# KMO_IO_MV1_3.net
KiCad netlist of a schematic drawn in EAGLE
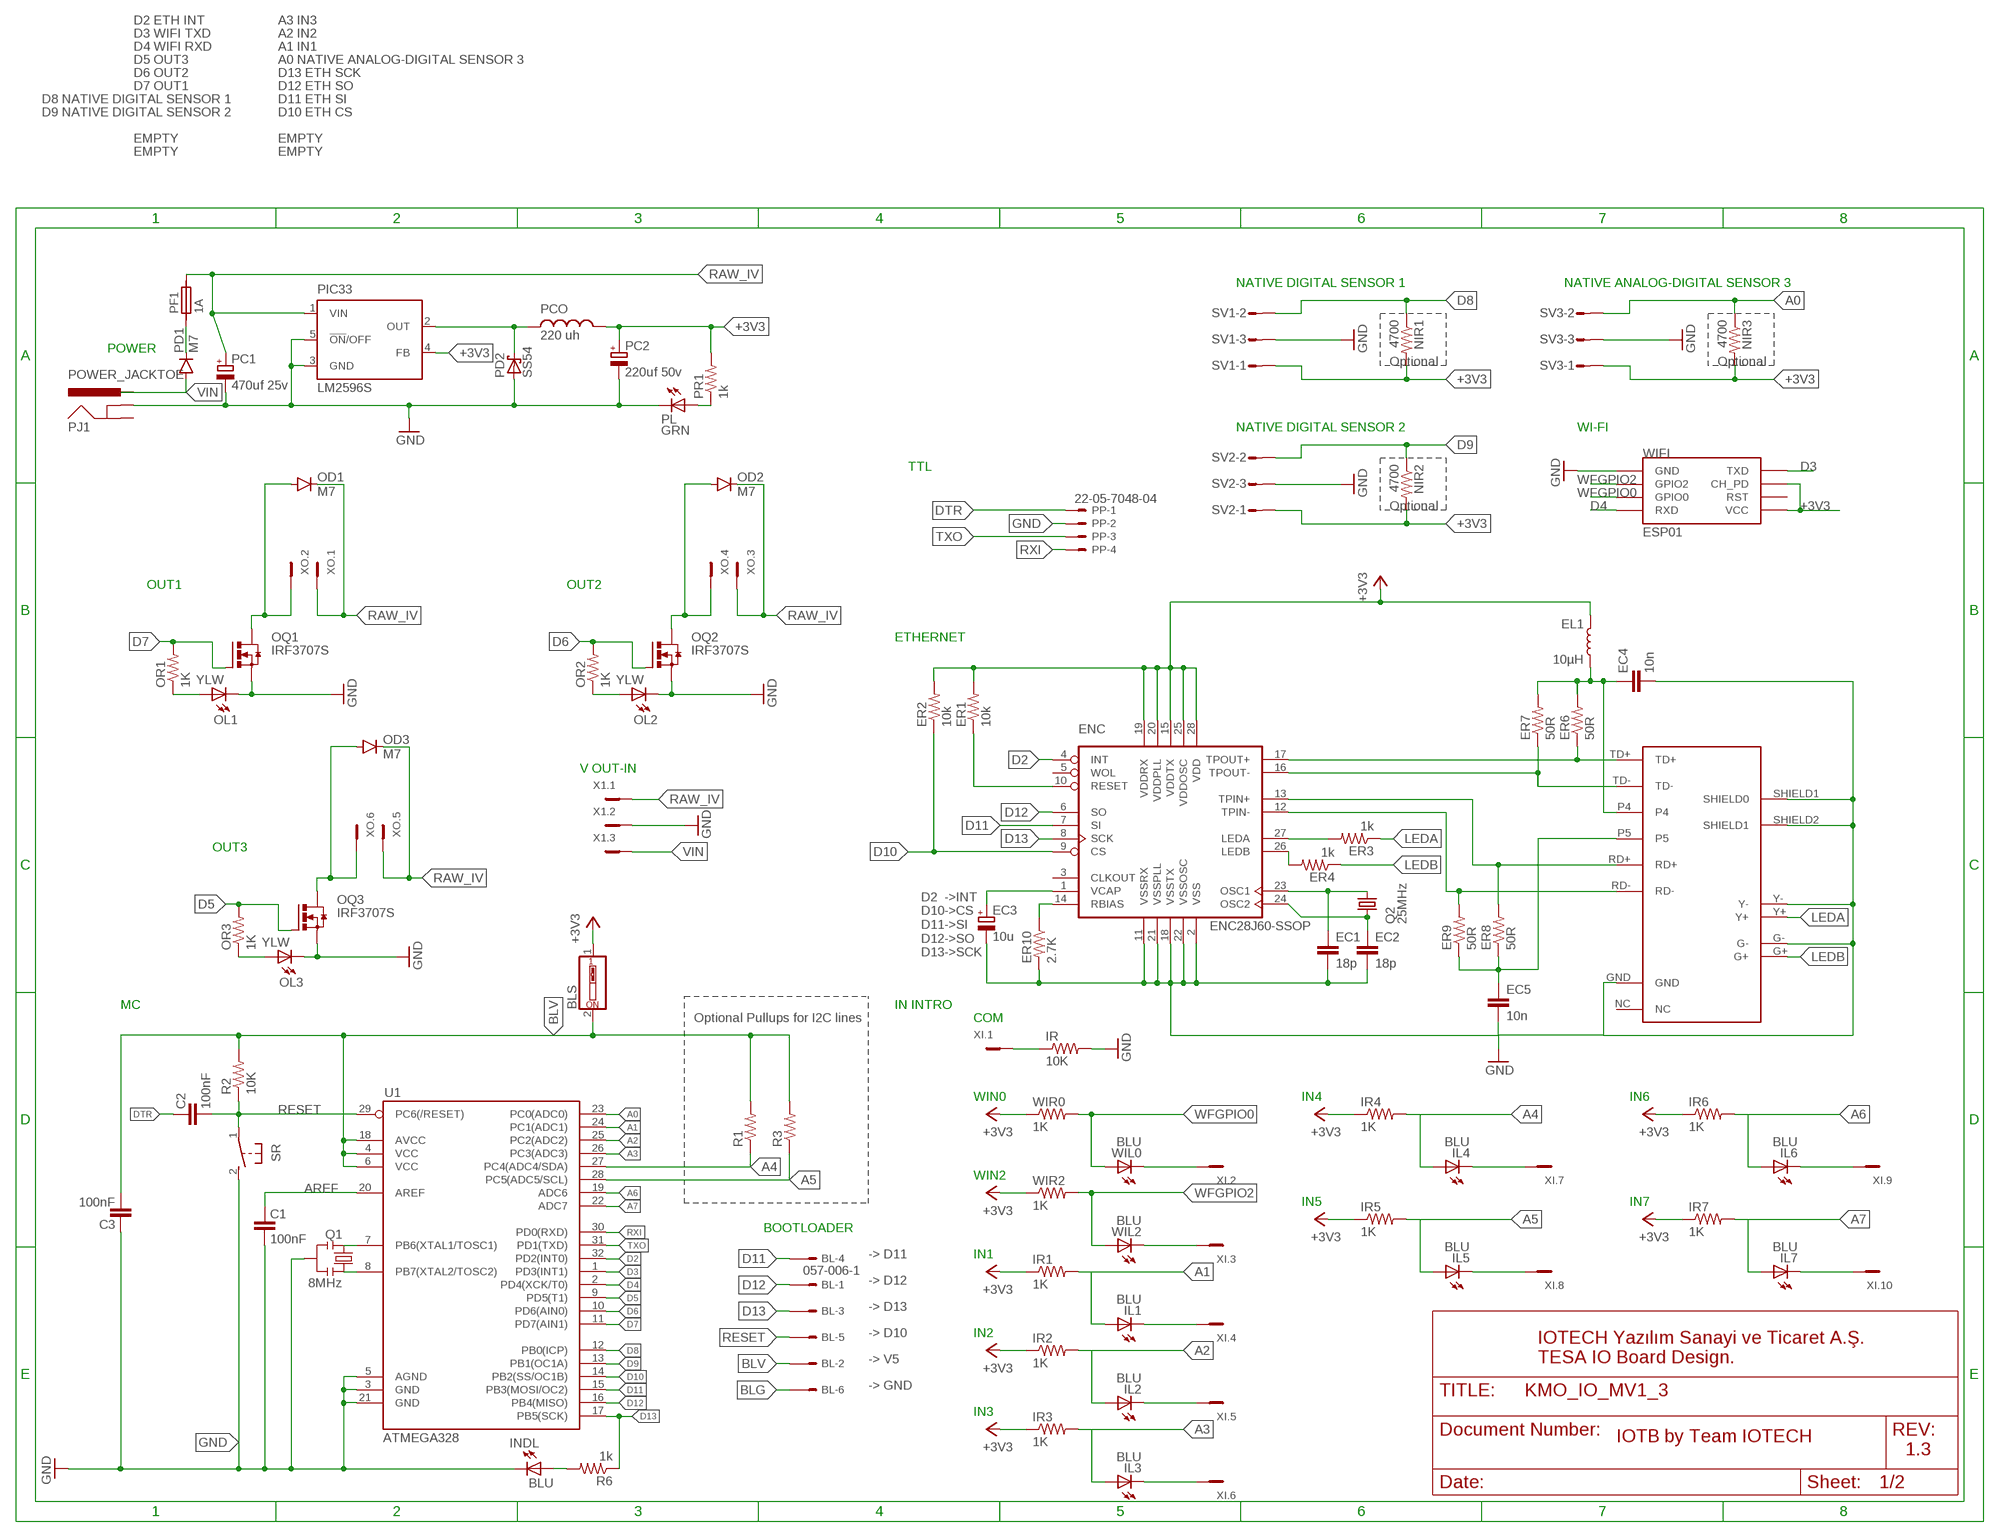
[diagram p0: schematic, sheet 1]
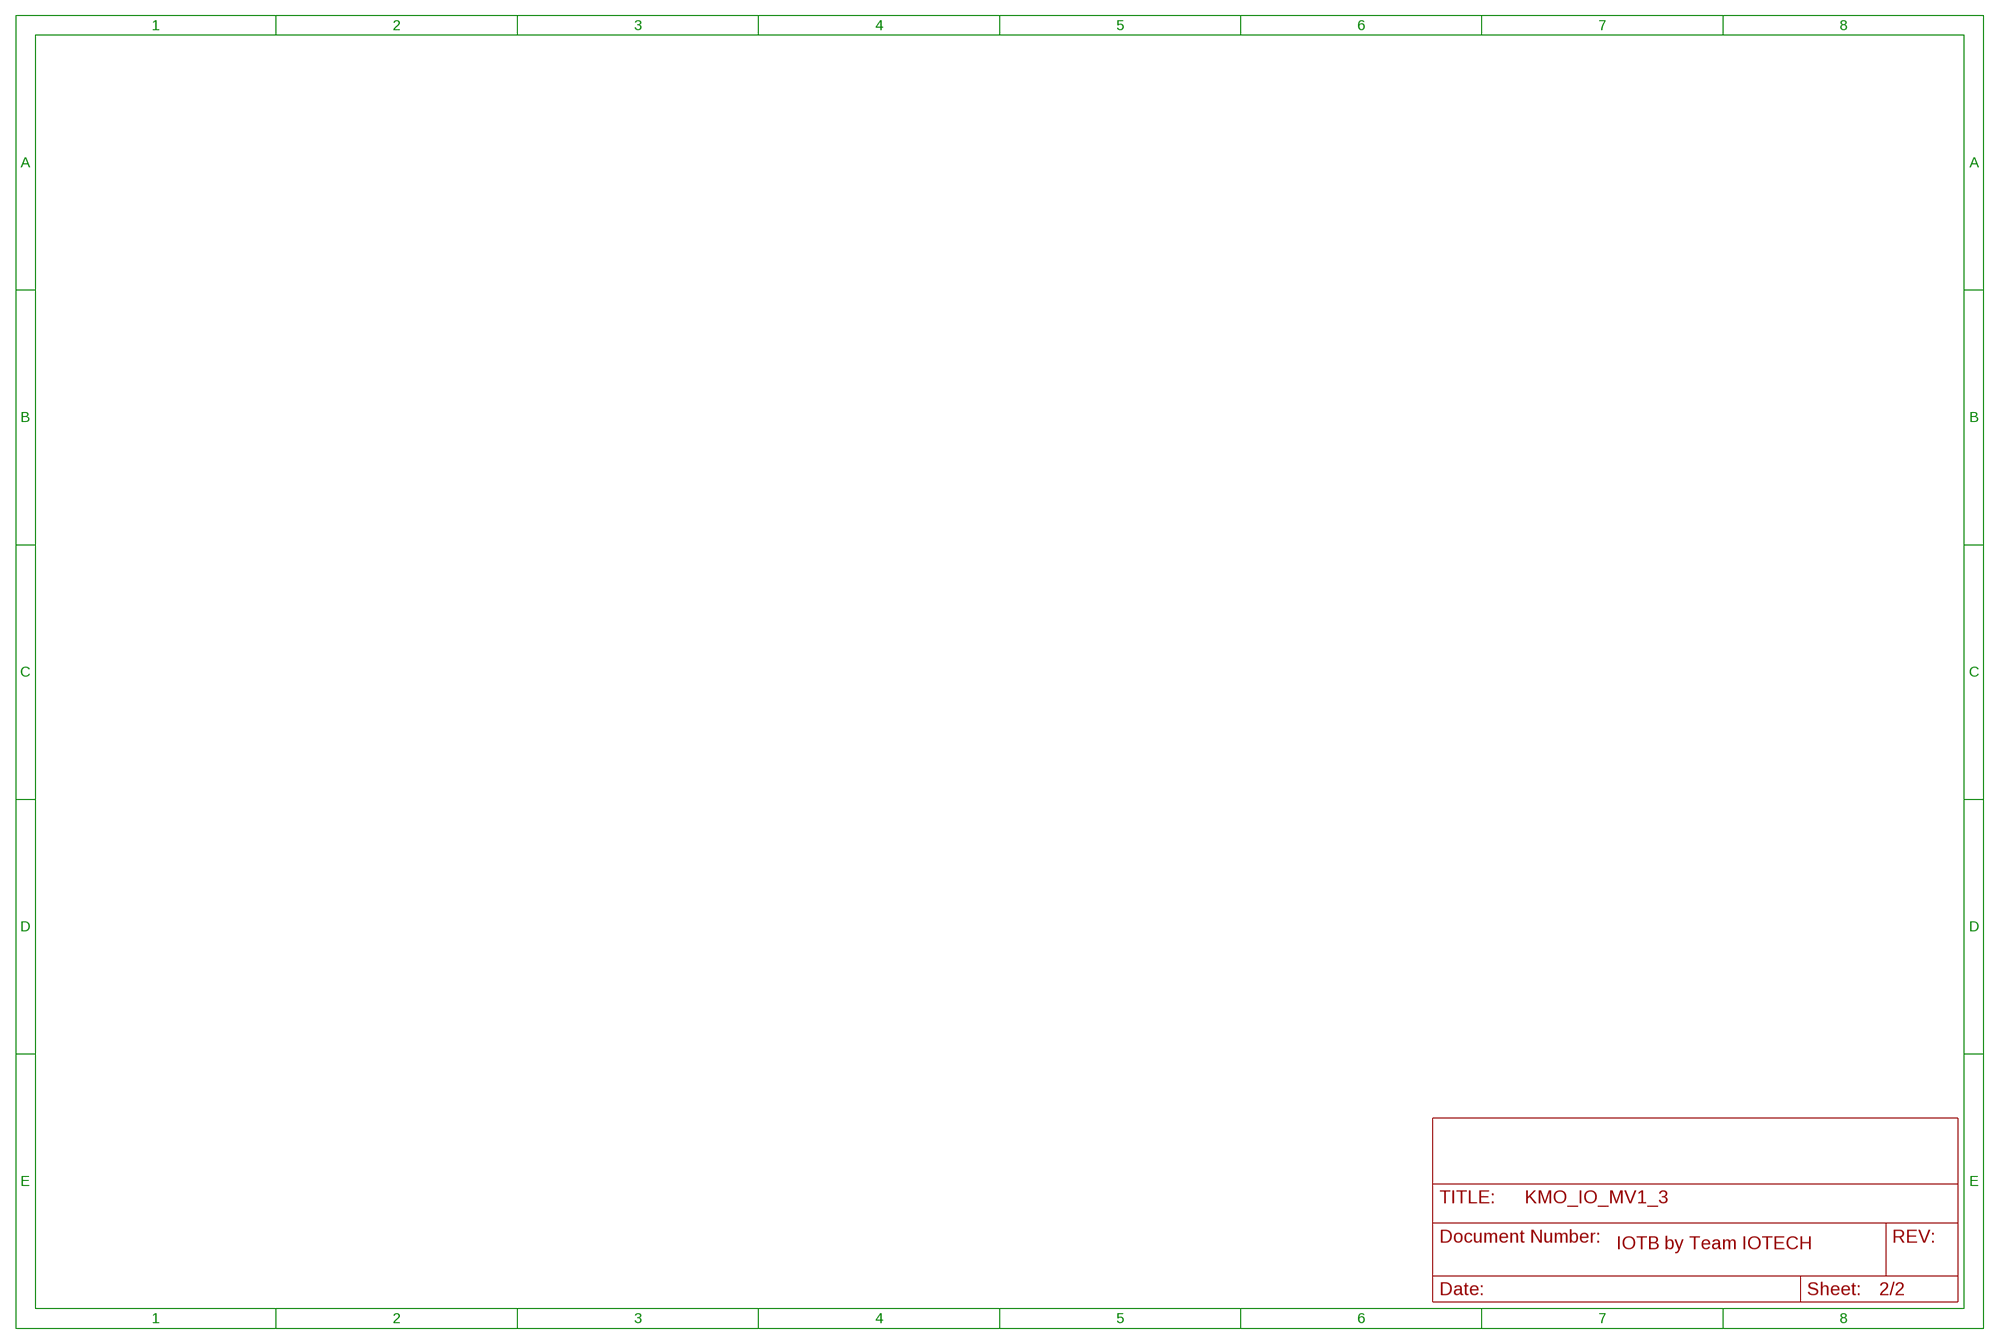
[diagram p1: schematic, sheet 2]

(export (version "E")
  (design (tool "Eeschema 10.0.6"))
  (components
    (comp (ref "BL")
      (value "057-006-1")
      (footprint "eagle-import:057-006-1")
      (libsource (lib "eagle-import") (part "057-006-1"))
    )
    (comp (ref "BLS")
      (value "SW_DIP-1")
      (footprint "eagle-import:EDG-01")
      (libsource (lib "eagle-import") (part "SW_DIP-1"))
    )
    (comp (ref "C1")
      (value "100nF")
      (footprint "eagle-import:0805")
      (libsource (lib "eagle-import") (part "CAP0805"))
    )
    (comp (ref "C2")
      (value "100nF")
      (footprint "eagle-import:0805")
      (libsource (lib "eagle-import") (part "CAP0805"))
    )
    (comp (ref "C3")
      (value "100nF")
      (footprint "eagle-import:0805")
      (libsource (lib "eagle-import") (part "CAP0805"))
    )
    (comp (ref "EC1")
      (value "18p")
      (footprint "eagle-import:0805")
      (libsource (lib "eagle-import") (part "CAP0805"))
    )
    (comp (ref "EC2")
      (value "18p")
      (footprint "eagle-import:0805")
      (libsource (lib "eagle-import") (part "CAP0805"))
    )
    (comp (ref "EC3")
      (value "10u")
      (footprint "eagle-import:CT3216")
      (libsource (lib "eagle-import") (part "CPOL-EUCT3216"))
    )
    (comp (ref "EC4")
      (value "10n")
      (footprint "eagle-import:0805")
      (libsource (lib "eagle-import") (part "CAP0805"))
    )
    (comp (ref "EC5")
      (value "10n")
      (footprint "eagle-import:0805")
      (libsource (lib "eagle-import") (part "CAP0805"))
    )
    (comp (ref "EL1")
      (value "10µH")
      (footprint "eagle-import:0805")
      (libsource (lib "eagle-import") (part "INDUCTOR-0805-3.3UH"))
    )
    (comp (ref "ENC")
      (value "ENC28J60-SSOP")
      (footprint "eagle-import:SSOP28")
      (libsource (lib "eagle-import") (part "ENC28J60-SSOP"))
    )
    (comp (ref "ER1")
      (value "10k")
      (footprint "eagle-import:0805")
      (libsource (lib "eagle-import") (part "RESISTOR0805-RES"))
    )
    (comp (ref "ER2")
      (value "10k")
      (footprint "eagle-import:0805")
      (libsource (lib "eagle-import") (part "RESISTOR0805-RES"))
    )
    (comp (ref "ER3")
      (value "1k")
      (footprint "eagle-import:0805")
      (libsource (lib "eagle-import") (part "RESISTOR0805-RES"))
    )
    (comp (ref "ER4")
      (value "1k")
      (footprint "eagle-import:0805")
      (libsource (lib "eagle-import") (part "RESISTOR0805-RES"))
    )
    (comp (ref "ER6")
      (value "50R")
      (footprint "eagle-import:0805")
      (libsource (lib "eagle-import") (part "RESISTOR0805-RES"))
    )
    (comp (ref "ER7")
      (value "50R")
      (footprint "eagle-import:0805")
      (libsource (lib "eagle-import") (part "RESISTOR0805-RES"))
    )
    (comp (ref "ER8")
      (value "50R")
      (footprint "eagle-import:0805")
      (libsource (lib "eagle-import") (part "RESISTOR0805-RES"))
    )
    (comp (ref "ER9")
      (value "50R")
      (footprint "eagle-import:0805")
      (libsource (lib "eagle-import") (part "RESISTOR0805-RES"))
    )
    (comp (ref "ER10")
      (value "2.7K")
      (footprint "eagle-import:0805")
      (libsource (lib "eagle-import") (part "RESISTOR0805-RES"))
    )
    (comp (ref "IL1")
      (value "BLU")
      (footprint "eagle-import:CHIP-LED0805")
      (libsource (lib "eagle-import") (part "LEDCHIP-LED0805"))
    )
    (comp (ref "IL2")
      (value "BLU")
      (footprint "eagle-import:CHIP-LED0805")
      (libsource (lib "eagle-import") (part "LEDCHIP-LED0805"))
    )
    (comp (ref "IL3")
      (value "BLU")
      (footprint "eagle-import:CHIP-LED0805")
      (libsource (lib "eagle-import") (part "LEDCHIP-LED0805"))
    )
    (comp (ref "IL4")
      (value "BLU")
      (footprint "eagle-import:CHIP-LED0805")
      (libsource (lib "eagle-import") (part "LEDCHIP-LED0805"))
    )
    (comp (ref "IL5")
      (value "BLU")
      (footprint "eagle-import:CHIP-LED0805")
      (libsource (lib "eagle-import") (part "LEDCHIP-LED0805"))
    )
    (comp (ref "IL6")
      (value "BLU")
      (footprint "eagle-import:CHIP-LED0805")
      (libsource (lib "eagle-import") (part "LEDCHIP-LED0805"))
    )
    (comp (ref "IL7")
      (value "BLU")
      (footprint "eagle-import:CHIP-LED0805")
      (libsource (lib "eagle-import") (part "LEDCHIP-LED0805"))
    )
    (comp (ref "INDL")
      (value "BLU")
      (footprint "eagle-import:CHIP-LED0805")
      (libsource (lib "eagle-import") (part "LEDCHIP-LED0805"))
    )
    (comp (ref "IR")
      (value "10K")
      (footprint "eagle-import:0805")
      (libsource (lib "eagle-import") (part "RESISTOR0805-RES"))
    )
    (comp (ref "IR1")
      (value "1K")
      (footprint "eagle-import:0805")
      (libsource (lib "eagle-import") (part "RESISTOR0805-RES"))
    )
    (comp (ref "IR2")
      (value "1K")
      (footprint "eagle-import:0805")
      (libsource (lib "eagle-import") (part "RESISTOR0805-RES"))
    )
    (comp (ref "IR3")
      (value "1K")
      (footprint "eagle-import:0805")
      (libsource (lib "eagle-import") (part "RESISTOR0805-RES"))
    )
    (comp (ref "IR4")
      (value "1K")
      (footprint "eagle-import:0805")
      (libsource (lib "eagle-import") (part "RESISTOR0805-RES"))
    )
    (comp (ref "IR5")
      (value "1K")
      (footprint "eagle-import:0805")
      (libsource (lib "eagle-import") (part "RESISTOR0805-RES"))
    )
    (comp (ref "IR6")
      (value "1K")
      (footprint "eagle-import:0805")
      (libsource (lib "eagle-import") (part "RESISTOR0805-RES"))
    )
    (comp (ref "IR7")
      (value "1K")
      (footprint "eagle-import:0805")
      (libsource (lib "eagle-import") (part "RESISTOR0805-RES"))
    )
    (comp (ref "NIR1")
      (value "4700")
      (footprint "eagle-import:0805")
      (libsource (lib "eagle-import") (part "RESISTOR0805-RES"))
    )
    (comp (ref "NIR2")
      (value "4700")
      (footprint "eagle-import:0805")
      (libsource (lib "eagle-import") (part "RESISTOR0805-RES"))
    )
    (comp (ref "NIR3")
      (value "4700")
      (footprint "eagle-import:0805")
      (libsource (lib "eagle-import") (part "RESISTOR0805-RES"))
    )
    (comp (ref "OD1")
      (value "M7")
      (footprint "eagle-import:SMA-DIODE")
      (libsource (lib "eagle-import") (part "DIODESMA"))
    )
    (comp (ref "OD2")
      (value "M7")
      (footprint "eagle-import:SMA-DIODE")
      (libsource (lib "eagle-import") (part "DIODESMA"))
    )
    (comp (ref "OD3")
      (value "M7")
      (footprint "eagle-import:SMA-DIODE")
      (libsource (lib "eagle-import") (part "DIODESMA"))
    )
    (comp (ref "OL1")
      (value "YLW")
      (footprint "eagle-import:CHIP-LED0805")
      (libsource (lib "eagle-import") (part "LEDCHIP-LED0805"))
    )
    (comp (ref "OL2")
      (value "YLW")
      (footprint "eagle-import:CHIP-LED0805")
      (libsource (lib "eagle-import") (part "LEDCHIP-LED0805"))
    )
    (comp (ref "OL3")
      (value "YLW")
      (footprint "eagle-import:CHIP-LED0805")
      (libsource (lib "eagle-import") (part "LEDCHIP-LED0805"))
    )
    (comp (ref "OQ1")
      (value "IRF3707S")
      (footprint "eagle-import:D2PACK")
      (libsource (lib "eagle-import") (part "IRF3704S"))
    )
    (comp (ref "OQ2")
      (value "IRF3707S")
      (footprint "eagle-import:D2PACK")
      (libsource (lib "eagle-import") (part "IRF3704S"))
    )
    (comp (ref "OQ3")
      (value "IRF3707S")
      (footprint "eagle-import:D2PACK")
      (libsource (lib "eagle-import") (part "IRF3704S"))
    )
    (comp (ref "OR1")
      (value "1K")
      (footprint "eagle-import:0805")
      (libsource (lib "eagle-import") (part "RESISTOR0805-RES"))
    )
    (comp (ref "OR2")
      (value "1K")
      (footprint "eagle-import:0805")
      (libsource (lib "eagle-import") (part "RESISTOR0805-RES"))
    )
    (comp (ref "OR3")
      (value "1K")
      (footprint "eagle-import:0805")
      (libsource (lib "eagle-import") (part "RESISTOR0805-RES"))
    )
    (comp (ref "PC1")
      (value "470uf 25v")
      (footprint "eagle-import:140CLH-1010")
      (libsource (lib "eagle-import") (part "CPOL-EU140CLH-1010"))
    )
    (comp (ref "PC2")
      (value "220uf 50v")
      (footprint "eagle-import:140CLH-1010")
      (libsource (lib "eagle-import") (part "CPOL-EU140CLH-1010"))
    )
    (comp (ref "PCO")
      (value "220 uh")
      (footprint "eagle-import:MSS1260")
      (libsource (lib "eagle-import") (part "MSS1260"))
    )
    (comp (ref "PD1")
      (value "M7")
      (footprint "eagle-import:SMA-DIODE")
      (libsource (lib "eagle-import") (part "DIODESMA"))
    )
    (comp (ref "PD2")
      (value "SS54")
      (footprint "eagle-import:SMB")
      (libsource (lib "eagle-import") (part "SCHOTTKY-DIODESMD"))
    )
    (comp (ref "PF1")
      (value "1A")
      (footprint "eagle-import:1820")
      (libsource (lib "eagle-import") (part "SIBA194600"))
    )
    (comp (ref "PIC33")
      (value "LM2596S")
      (footprint "eagle-import:TO263-5")
      (fields (field (name "MF") "NATIONAL SEMICONDUCTOR") (field (name "MPN") "LM2596S-ADJ/NOPB"))
      (libsource (lib "eagle-import") (part "LM2596S"))
    )
    (comp (ref "PJ1")
      (value "POWER_JACKTOE")
      (footprint "eagle-import:POWER_JACK_SMD_OVERPASTE_TOE")
      (libsource (lib "eagle-import") (part "POWER_JACKTOE"))
    )
    (comp (ref "PL")
      (value "GRN")
      (footprint "eagle-import:CHIP-LED0805")
      (libsource (lib "eagle-import") (part "LEDCHIP-LED0805"))
    )
    (comp (ref "PP")
      (value "22-05-7048-04")
      (footprint "eagle-import:7395-04")
      (fields (field (name "MF") "MOLEX"))
      (libsource (lib "eagle-import") (part "22-?-0405-7048"))
    )
    (comp (ref "PR1")
      (value "1k")
      (footprint "eagle-import:0805")
      (libsource (lib "eagle-import") (part "RESISTOR0805-RES"))
    )
    (comp (ref "Q1")
      (value "8MHz")
      (footprint "eagle-import:RESONATOR-SMD-1_1")
      (libsource (lib "eagle-import") (part "RESONATOR1{colon}1"))
    )
    (comp (ref "Q2")
      (value "25MHz")
      (footprint "eagle-import:5.0X3.2_2")
      (libsource (lib "eagle-import") (part "KX-9B"))
    )
    (comp (ref "R1")
      (value "RESISTOR0805-RES")
      (footprint "eagle-import:0805")
      (libsource (lib "eagle-import") (part "RESISTOR0805-RES"))
    )
    (comp (ref "R2")
      (value "10K")
      (footprint "eagle-import:0805")
      (libsource (lib "eagle-import") (part "RESISTOR0805-RES"))
    )
    (comp (ref "R3")
      (value "RESISTOR0805-RES")
      (footprint "eagle-import:0805")
      (libsource (lib "eagle-import") (part "RESISTOR0805-RES"))
    )
    (comp (ref "R6")
      (value "1k")
      (footprint "eagle-import:0805")
      (libsource (lib "eagle-import") (part "RESISTOR0805-RES"))
    )
    (comp (ref "SR")
      (value "31-XX")
      (footprint "eagle-import:B3F-31XX")
      (fields (field (name "MPN") "B3F-3100"))
      (libsource (lib "eagle-import") (part "31-XX"))
    )
    (comp (ref "SV1")
      (value "S03P")
      (footprint "eagle-import:S03P")
      (libsource (lib "eagle-import") (part "S03P"))
    )
    (comp (ref "SV2")
      (value "S03P")
      (footprint "eagle-import:S03P")
      (libsource (lib "eagle-import") (part "S03P"))
    )
    (comp (ref "SV3")
      (value "S03P")
      (footprint "eagle-import:S03P")
      (libsource (lib "eagle-import") (part "S03P"))
    )
    (comp (ref "U$2")
      (value "HR911105A")
      (footprint "eagle-import:RJ45")
      (libsource (lib "eagle-import") (part "HR911105A"))
    )
    (comp (ref "U1")
      (value "ATMEGA328")
      (footprint "eagle-import:TQFP32-08")
      (libsource (lib "eagle-import") (part "ATMEGA168"))
    )
    (comp (ref "WIFI")
      (value "ESP01")
      (footprint "eagle-import:ESP01")
      (libsource (lib "eagle-import") (part "ESP01"))
    )
    (comp (ref "WIL0")
      (value "BLU")
      (footprint "eagle-import:CHIP-LED0805")
      (libsource (lib "eagle-import") (part "LEDCHIP-LED0805"))
    )
    (comp (ref "WIL2")
      (value "BLU")
      (footprint "eagle-import:CHIP-LED0805")
      (libsource (lib "eagle-import") (part "LEDCHIP-LED0805"))
    )
    (comp (ref "WIR0")
      (value "1K")
      (footprint "eagle-import:0805")
      (libsource (lib "eagle-import") (part "RESISTOR0805-RES"))
    )
    (comp (ref "WIR2")
      (value "1K")
      (footprint "eagle-import:0805")
      (libsource (lib "eagle-import") (part "RESISTOR0805-RES"))
    )
    (comp (ref "X1")
      (value "MC3")
      (footprint "eagle-import:MC3")
      (libsource (lib "eagle-import") (part "MC3"))
    )
    (comp (ref "XI")
      (value "MC10")
      (footprint "eagle-import:MC10")
      (libsource (lib "eagle-import") (part "MC10"))
    )
    (comp (ref "XO")
      (value "MC6")
      (footprint "eagle-import:MC6")
      (libsource (lib "eagle-import") (part "MC6"))
    )
  )
  (nets
    (net (code "1") (name "+3V3") (class "Default")
      (node (ref "BLS") (pin "1") (pinfunction "1_1") (pintype "passive"))
      (node (ref "EL1") (pin "1") (pinfunction "1_1") (pintype "passive"))
      (node (ref "ENC") (pin "15") (pinfunction "VDDTX_15") (pintype "power_in"))
      (node (ref "ENC") (pin "19") (pinfunction "VDDRX_19") (pintype "power_in"))
      (node (ref "ENC") (pin "20") (pinfunction "VDDPLL_20") (pintype "power_in"))
      (node (ref "ENC") (pin "25") (pinfunction "VDDOSC_25") (pintype "power_in"))
      (node (ref "ENC") (pin "28") (pinfunction "VDD_28") (pintype "power_in"))
      (node (ref "ER1") (pin "2") (pinfunction "2_2") (pintype "passive"))
      (node (ref "ER2") (pin "2") (pinfunction "2_2") (pintype "passive"))
      (node (ref "IR1") (pin "1") (pinfunction "1_1") (pintype "passive"))
      (node (ref "IR2") (pin "1") (pinfunction "1_1") (pintype "passive"))
      (node (ref "IR3") (pin "1") (pinfunction "1_1") (pintype "passive"))
      (node (ref "IR4") (pin "1") (pinfunction "1_1") (pintype "passive"))
      (node (ref "IR5") (pin "1") (pinfunction "1_1") (pintype "passive"))
      (node (ref "IR6") (pin "1") (pinfunction "1_1") (pintype "passive"))
      (node (ref "IR7") (pin "1") (pinfunction "1_1") (pintype "passive"))
      (node (ref "NIR1") (pin "2") (pinfunction "2_2") (pintype "passive"))
      (node (ref "NIR2") (pin "2") (pinfunction "2_2") (pintype "passive"))
      (node (ref "NIR3") (pin "2") (pinfunction "2_2") (pintype "passive"))
      (node (ref "PC2") (pin "+") (pinfunction "+_+") (pintype "passive"))
      (node (ref "PCO") (pin "P$1") (pinfunction "P$1_P$1") (pintype "passive"))
      (node (ref "PIC33") (pin "4") (pinfunction "FB_4") (pintype "input"))
      (node (ref "PR1") (pin "2") (pinfunction "2_2") (pintype "passive"))
      (node (ref "SV1") (pin "1") (pinfunction "S_1") (pintype "passive"))
      (node (ref "SV2") (pin "1") (pinfunction "S_1") (pintype "passive"))
      (node (ref "SV3") (pin "1") (pinfunction "S_1") (pintype "passive"))
      (node (ref "WIFI") (pin "CH_PD") (pinfunction "CH_PD_CH_PD") (pintype "bidirectional"))
      (node (ref "WIFI") (pin "VCC") (pinfunction "VCC_VCC") (pintype "bidirectional"))
      (node (ref "WIR0") (pin "1") (pinfunction "1_1") (pintype "passive"))
      (node (ref "WIR2") (pin "1") (pinfunction "1_1") (pintype "passive"))
    )
    (net (code "2") (name "A0") (class "Default")
      (node (ref "NIR3") (pin "1") (pinfunction "1_1") (pintype "passive"))
      (node (ref "SV3") (pin "2") (pinfunction "S_2") (pintype "passive"))
      (node (ref "U1") (pin "23") (pinfunction "PC0(ADC0)_23") (pintype "bidirectional"))
    )
    (net (code "3") (name "A1") (class "Default")
      (node (ref "IL1") (pin "A") (pinfunction "A_A") (pintype "passive"))
      (node (ref "IR1") (pin "2") (pinfunction "2_2") (pintype "passive"))
      (node (ref "U1") (pin "24") (pinfunction "PC1(ADC1)_24") (pintype "bidirectional"))
    )
    (net (code "4") (name "A2") (class "Default")
      (node (ref "IL2") (pin "A") (pinfunction "A_A") (pintype "passive"))
      (node (ref "IR2") (pin "2") (pinfunction "2_2") (pintype "passive"))
      (node (ref "U1") (pin "25") (pinfunction "PC2(ADC2)_25") (pintype "bidirectional"))
    )
    (net (code "5") (name "A3") (class "Default")
      (node (ref "IL3") (pin "A") (pinfunction "A_A") (pintype "passive"))
      (node (ref "IR3") (pin "2") (pinfunction "2_2") (pintype "passive"))
      (node (ref "U1") (pin "26") (pinfunction "PC3(ADC3)_26") (pintype "bidirectional"))
    )
    (net (code "6") (name "A4") (class "Default")
      (node (ref "IL4") (pin "A") (pinfunction "A_A") (pintype "passive"))
      (node (ref "IR4") (pin "2") (pinfunction "2_2") (pintype "passive"))
      (node (ref "R1") (pin "1") (pinfunction "1_1") (pintype "passive"))
      (node (ref "U1") (pin "27") (pinfunction "PC4(ADC4/SDA)_27") (pintype "bidirectional"))
    )
    (net (code "7") (name "A5") (class "Default")
      (node (ref "IL5") (pin "A") (pinfunction "A_A") (pintype "passive"))
      (node (ref "IR5") (pin "2") (pinfunction "2_2") (pintype "passive"))
      (node (ref "R3") (pin "1") (pinfunction "1_1") (pintype "passive"))
      (node (ref "U1") (pin "28") (pinfunction "PC5(ADC5/SCL)_28") (pintype "bidirectional"))
    )
    (net (code "8") (name "A6") (class "Default")
      (node (ref "IL6") (pin "A") (pinfunction "A_A") (pintype "passive"))
      (node (ref "IR6") (pin "2") (pinfunction "2_2") (pintype "passive"))
      (node (ref "U1") (pin "19") (pinfunction "ADC6_19") (pintype "bidirectional"))
    )
    (net (code "9") (name "A7") (class "Default")
      (node (ref "IL7") (pin "A") (pinfunction "A_A") (pintype "passive"))
      (node (ref "IR7") (pin "2") (pinfunction "2_2") (pintype "passive"))
      (node (ref "U1") (pin "22") (pinfunction "ADC7_22") (pintype "bidirectional"))
    )
    (net (code "10") (name "AREF") (class "Default")
      (node (ref "C1") (pin "2") (pinfunction "2_2") (pintype "passive"))
      (node (ref "U1") (pin "20") (pinfunction "AREF_20") (pintype "bidirectional"))
    )
    (net (code "11") (name "BLG") (class "Default")
      (node (ref "BL") (pin "6") (pinfunction "S_6") (pintype "passive"))
    )
    (net (code "12") (name "BLV") (class "Default")
      (node (ref "BL") (pin "2") (pinfunction "S_2") (pintype "passive"))
      (node (ref "BLS") (pin "2") (pinfunction "2_2") (pintype "passive"))
      (node (ref "C3") (pin "1") (pinfunction "1_1") (pintype "passive"))
      (node (ref "R1") (pin "2") (pinfunction "2_2") (pintype "passive"))
      (node (ref "R2") (pin "2") (pinfunction "2_2") (pintype "passive"))
      (node (ref "R3") (pin "2") (pinfunction "2_2") (pintype "passive"))
      (node (ref "U1") (pin "18") (pinfunction "AVCC_18") (pintype "bidirectional"))
      (node (ref "U1") (pin "4") (pinfunction "VCC_4") (pintype "bidirectional"))
      (node (ref "U1") (pin "6") (pinfunction "VCC_6") (pintype "bidirectional"))
    )
    (net (code "13") (name "D2") (class "Default")
      (node (ref "ENC") (pin "4") (pinfunction "INT_4") (pintype "output"))
      (node (ref "U1") (pin "32") (pinfunction "PD2(INT0)_32") (pintype "bidirectional"))
    )
    (net (code "14") (name "D3") (class "Default")
      (node (ref "U1") (pin "1") (pinfunction "PD3(INT1)_1") (pintype "bidirectional"))
      (node (ref "WIFI") (pin "TX") (pinfunction "TXD_TX") (pintype "bidirectional"))
    )
    (net (code "15") (name "D4") (class "Default")
      (node (ref "U1") (pin "2") (pinfunction "PD4(XCK/T0)_2") (pintype "bidirectional"))
      (node (ref "WIFI") (pin "RX") (pinfunction "RXD_RX") (pintype "bidirectional"))
    )
    (net (code "16") (name "D5") (class "Default")
      (node (ref "OQ3") (pin "1") (pinfunction "G_1") (pintype "passive"))
      (node (ref "OR3") (pin "2") (pinfunction "2_2") (pintype "passive"))
      (node (ref "U1") (pin "9") (pinfunction "PD5(T1)_9") (pintype "bidirectional"))
    )
    (net (code "17") (name "D6") (class "Default")
      (node (ref "OQ2") (pin "1") (pinfunction "G_1") (pintype "passive"))
      (node (ref "OR2") (pin "2") (pinfunction "2_2") (pintype "passive"))
      (node (ref "U1") (pin "10") (pinfunction "PD6(AIN0)_10") (pintype "bidirectional"))
    )
    (net (code "18") (name "D7") (class "Default")
      (node (ref "OQ1") (pin "1") (pinfunction "G_1") (pintype "passive"))
      (node (ref "OR1") (pin "2") (pinfunction "2_2") (pintype "passive"))
      (node (ref "U1") (pin "11") (pinfunction "PD7(AIN1)_11") (pintype "bidirectional"))
    )
    (net (code "19") (name "D8") (class "Default")
      (node (ref "NIR1") (pin "1") (pinfunction "1_1") (pintype "passive"))
      (node (ref "SV1") (pin "2") (pinfunction "S_2") (pintype "passive"))
      (node (ref "U1") (pin "12") (pinfunction "PB0(ICP)_12") (pintype "bidirectional"))
    )
    (net (code "20") (name "D9") (class "Default")
      (node (ref "NIR2") (pin "1") (pinfunction "1_1") (pintype "passive"))
      (node (ref "SV2") (pin "2") (pinfunction "S_2") (pintype "passive"))
      (node (ref "U1") (pin "13") (pinfunction "PB1(OC1A)_13") (pintype "bidirectional"))
    )
    (net (code "21") (name "D10") (class "Default")
      (node (ref "ENC") (pin "9") (pinfunction "CS_9") (pintype "input"))
      (node (ref "ER2") (pin "1") (pinfunction "1_1") (pintype "passive"))
      (node (ref "U1") (pin "14") (pinfunction "PB2(SS/OC1B)_14") (pintype "bidirectional"))
    )
    (net (code "22") (name "D11") (class "Default")
      (node (ref "BL") (pin "4") (pinfunction "S_4") (pintype "passive"))
      (node (ref "ENC") (pin "7") (pinfunction "SI_7") (pintype "input"))
      (node (ref "U1") (pin "15") (pinfunction "PB3(MOSI/OC2)_15") (pintype "bidirectional"))
    )
    (net (code "23") (name "D12") (class "Default")
      (node (ref "BL") (pin "1") (pinfunction "S_1") (pintype "passive"))
      (node (ref "ENC") (pin "6") (pinfunction "SO_6") (pintype "output"))
      (node (ref "U1") (pin "16") (pinfunction "PB4(MISO)_16") (pintype "bidirectional"))
    )
    (net (code "24") (name "D13") (class "Default")
      (node (ref "BL") (pin "3") (pinfunction "S_3") (pintype "passive"))
      (node (ref "ENC") (pin "8") (pinfunction "SCK_8") (pintype "input"))
      (node (ref "R6") (pin "1") (pinfunction "1_1") (pintype "passive"))
      (node (ref "U1") (pin "17") (pinfunction "PB5(SCK)_17") (pintype "bidirectional"))
    )
    (net (code "25") (name "DTR") (class "Default")
      (node (ref "C2") (pin "2") (pinfunction "2_2") (pintype "passive"))
      (node (ref "PP") (pin "1") (pinfunction "S_1") (pintype "passive"))
    )
    (net (code "26") (name "GND") (class "Default")
      (node (ref "C1") (pin "1") (pinfunction "1_1") (pintype "passive"))
      (node (ref "C3") (pin "2") (pinfunction "2_2") (pintype "passive"))
      (node (ref "EC1") (pin "2") (pinfunction "2_2") (pintype "passive"))
      (node (ref "EC2") (pin "2") (pinfunction "2_2") (pintype "passive"))
      (node (ref "EC3") (pin "-") (pinfunction "-_-") (pintype "passive"))
      (node (ref "EC4") (pin "2") (pinfunction "2_2") (pintype "passive"))
      (node (ref "EC5") (pin "2") (pinfunction "2_2") (pintype "passive"))
      (node (ref "ENC") (pin "11") (pinfunction "VSSRX_11") (pintype "power_in"))
      (node (ref "ENC") (pin "18") (pinfunction "VSSTX_18") (pintype "power_in"))
      (node (ref "ENC") (pin "2") (pinfunction "VSS_2") (pintype "power_in"))
      (node (ref "ENC") (pin "21") (pinfunction "VSSPLL_21") (pintype "power_in"))
      (node (ref "ENC") (pin "22") (pinfunction "VSSOSC_22") (pintype "power_in"))
      (node (ref "ER10") (pin "2") (pinfunction "2_2") (pintype "passive"))
      (node (ref "INDL") (pin "C") (pinfunction "C_C") (pintype "passive"))
      (node (ref "IR") (pin "2") (pinfunction "2_2") (pintype "passive"))
      (node (ref "OL1") (pin "C") (pinfunction "C_C") (pintype "passive"))
      (node (ref "OL2") (pin "C") (pinfunction "C_C") (pintype "passive"))
      (node (ref "OL3") (pin "C") (pinfunction "C_C") (pintype "passive"))
      (node (ref "OQ1") (pin "3") (pinfunction "S_3") (pintype "passive"))
      (node (ref "OQ2") (pin "3") (pinfunction "S_3") (pintype "passive"))
      (node (ref "OQ3") (pin "3") (pinfunction "S_3") (pintype "passive"))
      (node (ref "PC1") (pin "-") (pinfunction "-_-") (pintype "passive"))
      (node (ref "PC2") (pin "-") (pinfunction "-_-") (pintype "passive"))
      (node (ref "PD2") (pin "A") (pinfunction "A_A") (pintype "passive"))
      (node (ref "PIC33") (pin "3") (pinfunction "GND_3") (pintype "power_in"))
      (node (ref "PIC33") (pin "5") (pinfunction "~{ON}/OFF_5") (pintype "input"))
      (node (ref "PJ1") (pin "GND") (pinfunction "GNDBREAK_GND") (pintype "bidirectional"))
      (node (ref "PL") (pin "C") (pinfunction "C_C") (pintype "passive"))
      (node (ref "PP") (pin "2") (pinfunction "S_2") (pintype "passive"))
      (node (ref "Q1") (pin "2") (pinfunction "2_2") (pintype "passive"))
      (node (ref "SR") (pin "2") (pinfunction "S_2") (pintype "passive"))
      (node (ref "SV1") (pin "3") (pinfunction "S_3") (pintype "passive"))
      (node (ref "SV2") (pin "3") (pinfunction "S_3") (pintype "passive"))
      (node (ref "SV3") (pin "3") (pinfunction "S_3") (pintype "passive"))
      (node (ref "U$2") (pin "G-") (pinfunction "G-_G-") (pintype "bidirectional"))
      (node (ref "U$2") (pin "GND") (pinfunction "GND_GND") (pintype "bidirectional"))
      (node (ref "U$2") (pin "SHIELD1") (pinfunction "SHIELD0_SHIELD1") (pintype "bidirectional"))
      (node (ref "U$2") (pin "SHIELD2") (pinfunction "SHIELD1_SHIELD2") (pintype "bidirectional"))
      (node (ref "U$2") (pin "Y-") (pinfunction "Y-_Y-") (pintype "bidirectional"))
      (node (ref "U1") (pin "21") (pinfunction "GND_21") (pintype "bidirectional"))
      (node (ref "U1") (pin "3") (pinfunction "GND_3") (pintype "bidirectional"))
      (node (ref "U1") (pin "5") (pinfunction "AGND_5") (pintype "bidirectional"))
      (node (ref "WIFI") (pin "GND") (pinfunction "GND_GND") (pintype "bidirectional"))
      (node (ref "X1") (pin "2") (pinfunction "SK_2") (pintype "passive"))
    )
    (net (code "27") (name "LEDA") (class "Default")
      (node (ref "ER3") (pin "1") (pinfunction "1_1") (pintype "passive"))
      (node (ref "U$2") (pin "Y+") (pinfunction "Y+_Y+") (pintype "bidirectional"))
    )
    (net (code "28") (name "LEDB") (class "Default")
      (node (ref "ER4") (pin "1") (pinfunction "1_1") (pintype "passive"))
      (node (ref "U$2") (pin "G+") (pinfunction "G+_G+") (pintype "bidirectional"))
    )
    (net (code "29") (name "Net-(EC4-Pad1)") (class "Default")
      (node (ref "EC4") (pin "1") (pinfunction "1_1") (pintype "passive"))
      (node (ref "EL1") (pin "2") (pinfunction "2_2") (pintype "passive"))
      (node (ref "ER6") (pin "2") (pinfunction "2_2") (pintype "passive"))
      (node (ref "ER7") (pin "2") (pinfunction "2_2") (pintype "passive"))
      (node (ref "U$2") (pin "P4") (pinfunction "P4_P4") (pintype "bidirectional"))
    )
    (net (code "30") (name "Net-(EC5-Pad1)") (class "Default")
      (node (ref "EC5") (pin "1") (pinfunction "1_1") (pintype "passive"))
      (node (ref "ER8") (pin "1") (pinfunction "1_1") (pintype "passive"))
      (node (ref "ER9") (pin "1") (pinfunction "1_1") (pintype "passive"))
      (node (ref "U$2") (pin "P5") (pinfunction "P5_P5") (pintype "bidirectional"))
    )
    (net (code "31") (name "Net-(ENC-LEDA)") (class "Default")
      (node (ref "ENC") (pin "27") (pinfunction "LEDA_27") (pintype "output"))
      (node (ref "ER3") (pin "2") (pinfunction "2_2") (pintype "passive"))
    )
    (net (code "32") (name "Net-(ENC-LEDB)") (class "Default")
      (node (ref "ENC") (pin "26") (pinfunction "LEDB_26") (pintype "output"))
      (node (ref "ER4") (pin "2") (pinfunction "2_2") (pintype "passive"))
    )
    (net (code "33") (name "Net-(ENC-OSC1)") (class "Default")
      (node (ref "EC1") (pin "1") (pinfunction "1_1") (pintype "passive"))
      (node (ref "ENC") (pin "23") (pinfunction "OSC1_23") (pintype "input"))
      (node (ref "Q2") (pin "2") (pinfunction "2_2") (pintype "passive"))
    )
    (net (code "34") (name "Net-(ENC-OSC2)") (class "Default")
      (node (ref "EC2") (pin "1") (pinfunction "1_1") (pintype "passive"))
      (node (ref "ENC") (pin "24") (pinfunction "OSC2_24") (pintype "output"))
      (node (ref "Q2") (pin "1") (pinfunction "1_1") (pintype "passive"))
    )
    (net (code "35") (name "Net-(ENC-RBIAS)") (class "Default")
      (node (ref "ENC") (pin "14") (pinfunction "RBIAS_14") (pintype "passive"))
      (node (ref "ER10") (pin "1") (pinfunction "1_1") (pintype "passive"))
    )
    (net (code "36") (name "Net-(ENC-RESET)") (class "Default")
      (node (ref "ENC") (pin "10") (pinfunction "RESET_10") (pintype "input"))
      (node (ref "ER1") (pin "1") (pinfunction "1_1") (pintype "passive"))
    )
    (net (code "37") (name "Net-(ENC-TPIN+)") (class "Default")
      (node (ref "ENC") (pin "13") (pinfunction "TPIN+_13") (pintype "input"))
      (node (ref "ER8") (pin "2") (pinfunction "2_2") (pintype "passive"))
      (node (ref "U$2") (pin "RD+") (pinfunction "RD+_RD+") (pintype "bidirectional"))
    )
    (net (code "38") (name "Net-(ENC-TPIN-)") (class "Default")
      (node (ref "ENC") (pin "12") (pinfunction "TPIN-_12") (pintype "input"))
      (node (ref "ER9") (pin "2") (pinfunction "2_2") (pintype "passive"))
      (node (ref "U$2") (pin "RD-") (pinfunction "RD-_RD-") (pintype "bidirectional"))
    )
    (net (code "39") (name "Net-(ENC-TPOUT+)") (class "Default")
      (node (ref "ENC") (pin "17") (pinfunction "TPOUT+_17") (pintype "output"))
      (node (ref "ER6") (pin "1") (pinfunction "1_1") (pintype "passive"))
      (node (ref "U$2") (pin "TD+") (pinfunction "TD+_TD+") (pintype "bidirectional"))
    )
    (net (code "40") (name "Net-(ENC-TPOUT-)") (class "Default")
      (node (ref "ENC") (pin "16") (pinfunction "TPOUT-_16") (pintype "output"))
      (node (ref "ER7") (pin "1") (pinfunction "1_1") (pintype "passive"))
      (node (ref "U$2") (pin "TD-") (pinfunction "TD-_TD-") (pintype "bidirectional"))
    )
    (net (code "41") (name "Net-(ENC-VCAP)") (class "Default")
      (node (ref "EC3") (pin "+") (pinfunction "+_+") (pintype "passive"))
      (node (ref "ENC") (pin "1") (pinfunction "VCAP_1") (pintype "power_in"))
    )
    (net (code "42") (name "Net-(INDL-PadA)") (class "Default")
      (node (ref "INDL") (pin "A") (pinfunction "A_A") (pintype "passive"))
      (node (ref "R6") (pin "2") (pinfunction "2_2") (pintype "passive"))
    )
    (net (code "43") (name "Net-(OL1-PadA)") (class "Default")
      (node (ref "OL1") (pin "A") (pinfunction "A_A") (pintype "passive"))
      (node (ref "OR1") (pin "1") (pinfunction "1_1") (pintype "passive"))
    )
    (net (code "44") (name "Net-(OL2-PadA)") (class "Default")
      (node (ref "OL2") (pin "A") (pinfunction "A_A") (pintype "passive"))
      (node (ref "OR2") (pin "1") (pinfunction "1_1") (pintype "passive"))
    )
    (net (code "45") (name "Net-(OL3-PadA)") (class "Default")
      (node (ref "OL3") (pin "A") (pinfunction "A_A") (pintype "passive"))
      (node (ref "OR3") (pin "1") (pinfunction "1_1") (pintype "passive"))
    )
    (net (code "46") (name "Net-(OQ1-D)") (class "Default")
      (node (ref "OD1") (pin "A") (pinfunction "A_A") (pintype "passive"))
      (node (ref "OQ1") (pin "2") (pinfunction "D_2") (pintype "passive"))
      (node (ref "XO") (pin "2") (pinfunction "SK_2") (pintype "passive"))
    )
    (net (code "47") (name "Net-(OQ2-D)") (class "Default")
      (node (ref "OD2") (pin "A") (pinfunction "A_A") (pintype "passive"))
      (node (ref "OQ2") (pin "2") (pinfunction "D_2") (pintype "passive"))
      (node (ref "XO") (pin "4") (pinfunction "SK_4") (pintype "passive"))
    )
    (net (code "48") (name "Net-(OQ3-D)") (class "Default")
      (node (ref "OD3") (pin "A") (pinfunction "A_A") (pintype "passive"))
      (node (ref "OQ3") (pin "2") (pinfunction "D_2") (pintype "passive"))
      (node (ref "XO") (pin "6") (pinfunction "SK_6") (pintype "passive"))
    )
    (net (code "49") (name "Net-(PD1-PadC)") (class "Default")
      (node (ref "PD1") (pin "C") (pinfunction "C_C") (pintype "passive"))
      (node (ref "PF1") (pin "1") (pinfunction "1_1") (pintype "passive"))
    )
    (net (code "50") (name "Net-(PIC33-OUT)") (class "Default")
      (node (ref "PCO") (pin "P$2") (pinfunction "P$2_P$2") (pintype "passive"))
      (node (ref "PD2") (pin "C") (pinfunction "C_C") (pintype "passive"))
      (node (ref "PIC33") (pin "2") (pinfunction "OUT_2") (pintype "output"))
    )
    (net (code "51") (name "Net-(PL-PadA)") (class "Default")
      (node (ref "PL") (pin "A") (pinfunction "A_A") (pintype "passive"))
      (node (ref "PR1") (pin "1") (pinfunction "1_1") (pintype "passive"))
    )
    (net (code "52") (name "Net-(U1-PB6(XTAL1{slash}TOSC1))") (class "Default")
      (node (ref "Q1") (pin "1") (pinfunction "1_1") (pintype "passive"))
      (node (ref "U1") (pin "7") (pinfunction "PB6(XTAL1/TOSC1)_7") (pintype "bidirectional"))
    )
    (net (code "53") (name "Net-(U1-PB7(XTAL2{slash}TOSC2))") (class "Default")
      (node (ref "Q1") (pin "3") (pinfunction "3_3") (pintype "passive"))
      (node (ref "U1") (pin "8") (pinfunction "PB7(XTAL2/TOSC2)_8") (pintype "bidirectional"))
    )
    (net (code "54") (name "Net-(XIA-SK)") (class "Default")
      (node (ref "IR") (pin "1") (pinfunction "1_1") (pintype "passive"))
      (node (ref "XI") (pin "1") (pinfunction "SK_1") (pintype "passive"))
    )
    (net (code "55") (name "Net-(XIB-SK)") (class "Default")
      (node (ref "IL7") (pin "C") (pinfunction "C_C") (pintype "passive"))
      (node (ref "XI") (pin "10") (pinfunction "SK_10") (pintype "passive"))
    )
    (net (code "56") (name "Net-(XIC-SK)") (class "Default")
      (node (ref "WIL0") (pin "C") (pinfunction "C_C") (pintype "passive"))
      (node (ref "XI") (pin "2") (pinfunction "SK_2") (pintype "passive"))
    )
    (net (code "57") (name "Net-(XID-SK)") (class "Default")
      (node (ref "WIL2") (pin "C") (pinfunction "C_C") (pintype "passive"))
      (node (ref "XI") (pin "3") (pinfunction "SK_3") (pintype "passive"))
    )
    (net (code "58") (name "Net-(XIE-SK)") (class "Default")
      (node (ref "IL1") (pin "C") (pinfunction "C_C") (pintype "passive"))
      (node (ref "XI") (pin "4") (pinfunction "SK_4") (pintype "passive"))
    )
    (net (code "59") (name "Net-(XIF-SK)") (class "Default")
      (node (ref "IL2") (pin "C") (pinfunction "C_C") (pintype "passive"))
      (node (ref "XI") (pin "5") (pinfunction "SK_5") (pintype "passive"))
    )
    (net (code "60") (name "Net-(XIG-SK)") (class "Default")
      (node (ref "IL3") (pin "C") (pinfunction "C_C") (pintype "passive"))
      (node (ref "XI") (pin "6") (pinfunction "SK_6") (pintype "passive"))
    )
    (net (code "61") (name "Net-(XIH-SK)") (class "Default")
      (node (ref "IL4") (pin "C") (pinfunction "C_C") (pintype "passive"))
      (node (ref "XI") (pin "7") (pinfunction "SK_7") (pintype "passive"))
    )
    (net (code "62") (name "Net-(XII-SK)") (class "Default")
      (node (ref "IL5") (pin "C") (pinfunction "C_C") (pintype "passive"))
      (node (ref "XI") (pin "8") (pinfunction "SK_8") (pintype "passive"))
    )
    (net (code "63") (name "Net-(XIJ-SK)") (class "Default")
      (node (ref "IL6") (pin "C") (pinfunction "C_C") (pintype "passive"))
      (node (ref "XI") (pin "9") (pinfunction "SK_9") (pintype "passive"))
    )
    (net (code "64") (name "RAW_IV") (class "Default")
      (node (ref "OD1") (pin "C") (pinfunction "C_C") (pintype "passive"))
      (node (ref "OD2") (pin "C") (pinfunction "C_C") (pintype "passive"))
      (node (ref "OD3") (pin "C") (pinfunction "C_C") (pintype "passive"))
      (node (ref "PC1") (pin "+") (pinfunction "+_+") (pintype "passive"))
      (node (ref "PF1") (pin "2") (pinfunction "2_2") (pintype "passive"))
      (node (ref "PIC33") (pin "1") (pinfunction "VIN_1") (pintype "input"))
      (node (ref "X1") (pin "1") (pinfunction "SK_1") (pintype "passive"))
      (node (ref "XO") (pin "1") (pinfunction "SK_1") (pintype "passive"))
      (node (ref "XO") (pin "3") (pinfunction "SK_3") (pintype "passive"))
      (node (ref "XO") (pin "5") (pinfunction "SK_5") (pintype "passive"))
    )
    (net (code "65") (name "RESET") (class "Default")
      (node (ref "BL") (pin "5") (pinfunction "S_5") (pintype "passive"))
      (node (ref "C2") (pin "1") (pinfunction "1_1") (pintype "passive"))
      (node (ref "R2") (pin "1") (pinfunction "1_1") (pintype "passive"))
      (node (ref "SR") (pin "1") (pinfunction "P_1") (pintype "passive"))
      (node (ref "U1") (pin "29") (pinfunction "PC6(/RESET)_29") (pintype "bidirectional"))
    )
    (net (code "66") (name "RXI") (class "Default")
      (node (ref "PP") (pin "4") (pinfunction "S_4") (pintype "passive"))
      (node (ref "U1") (pin "30") (pinfunction "PD0(RXD)_30") (pintype "bidirectional"))
    )
    (net (code "67") (name "TXO") (class "Default")
      (node (ref "PP") (pin "3") (pinfunction "S_3") (pintype "passive"))
      (node (ref "U1") (pin "31") (pinfunction "PD1(TXD)_31") (pintype "bidirectional"))
    )
    (net (code "68") (name "VIN") (class "Default")
      (node (ref "PD1") (pin "A") (pinfunction "A_A") (pintype "passive"))
      (node (ref "PJ1") (pin "VIN0") (pinfunction "PWR_VIN0") (pintype "bidirectional"))
      (node (ref "X1") (pin "3") (pinfunction "SK_3") (pintype "passive"))
    )
    (net (code "69") (name "WFGPIO0") (class "Default")
      (node (ref "WIFI") (pin "GPIO0") (pinfunction "GPIO0_GPIO0") (pintype "bidirectional"))
      (node (ref "WIL0") (pin "A") (pinfunction "A_A") (pintype "passive"))
      (node (ref "WIR0") (pin "2") (pinfunction "2_2") (pintype "passive"))
    )
    (net (code "70") (name "WFGPIO2") (class "Default")
      (node (ref "WIFI") (pin "GPIO2") (pinfunction "GPIO2_GPIO2") (pintype "bidirectional"))
      (node (ref "WIL2") (pin "A") (pinfunction "A_A") (pintype "passive"))
      (node (ref "WIR2") (pin "2") (pinfunction "2_2") (pintype "passive"))
    )
    (net (code "71") (name "unconnected-(ENC-CLKOUT-Pad3)") (class "Default")
      (node (ref "ENC") (pin "3") (pinfunction "CLKOUT_3") (pintype "output"))
    )
    (net (code "72") (name "unconnected-(ENC-WOL-Pad5)") (class "Default")
      (node (ref "ENC") (pin "5") (pinfunction "WOL_5") (pintype "output"))
    )
    (net (code "73") (name "unconnected-(PJ1-GND-PadP$4)") (class "Default")
      (node (ref "PJ1") (pin "P$4") (pinfunction "GND_P$4") (pintype "bidirectional"))
    )
    (net (code "74") (name "unconnected-(U$2-PadNC)") (class "Default")
      (node (ref "U$2") (pin "NC") (pinfunction "NC_NC") (pintype "bidirectional"))
    )
    (net (code "75") (name "unconnected-(WIFI-PadRST)") (class "Default")
      (node (ref "WIFI") (pin "RST") (pinfunction "RST_RST") (pintype "bidirectional"))
    )
  )
)
